# PCIe_USB30_Conn_Panel_Bottom.net
KiCad netlist of a schematic drawn in Altium Designer
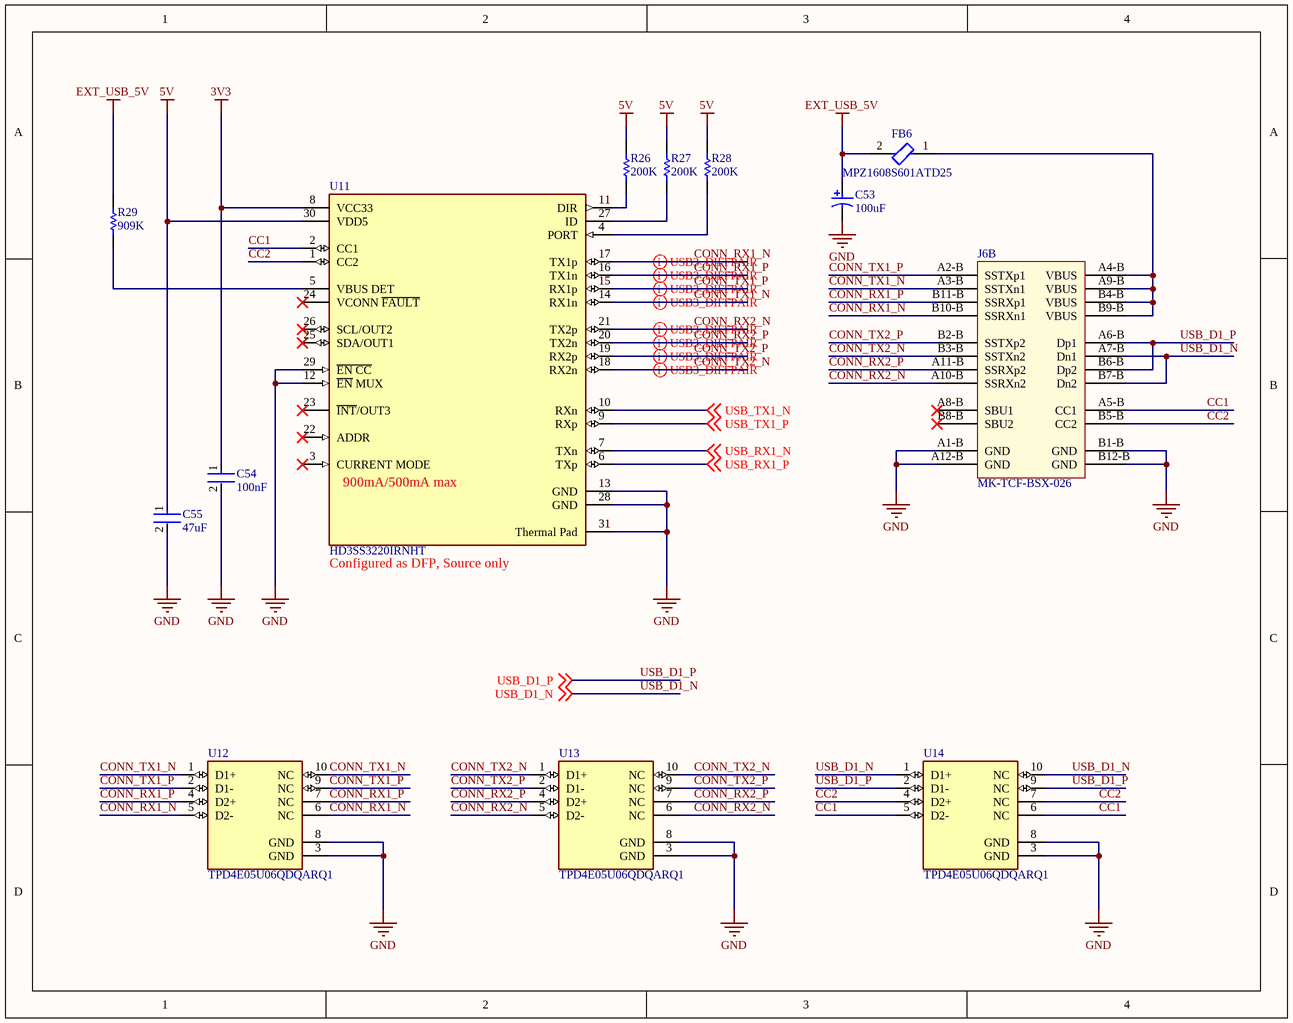
[diagram p0: PCIe_USB30_Conn_Panel_Bottom.SchDoc]

(export (version "E")
  (design (tool "Eeschema 10.0.6"))
  (components
    (comp (ref "C53")
      (value "100uF")
      (footprint "PNSC-EEEFK1C101P_L")
      (fields (field (name "MANUFACTURER") "Panasonic"))
      (libsource (lib "Altium Content Vault") (part "CAP-P-2"))
    )
    (comp (ref "C54")
      (value "100nF")
      (footprint "FP-C0402-BB-MFG")
      (description "CAP CER 0.1UF 10V X5R 0402")
      (fields (field (name "MANUFACTURER") "Kemet") (field (name "TOLERANCE") "0.1"))
      (libsource (lib "Altium Content Vault") (part "b4654b650e69147ec39a6b967a45e02"))
    )
    (comp (ref "C55")
      (value "47uF")
      (footprint "FP-C2012-125-0_2-IPC_B")
      (description "Multilayer Ceramic Capacitors 47μF ±20% 10V X5R SMD 0805")
      (fields (field (name "VOLTAGE") "10V") (field (name "TOLERANCE") "20%"))
      (libsource (lib "Altium Content Vault") (part "b4654b650e69147ec39a6b967a45e02"))
    )
    (comp (ref "FB6")
      (value "MPZ1608S601ATD25")
      (footprint "FP-MPZ1608-0_8-IPC_B")
      (description "Power line Ferrite Bead 600Ω @ 100MHz 1A DCR 0.15Ω AEC-Q200 SMD 0603")
      (fields (field (name "TOLERANCE") "25%"))
      (libsource (lib "Altium Content Vault") (part "5f30dd21d616792df468990f7003faa"))
    )
    (comp (ref "J6")
      (value "MK-TCF-BSX-026")
      (footprint "MK-TCF-BSX-026")
      (libsource (lib "MK-TCF-BSX-026") (part "MK-TCF-BSX-026"))
    )
    (comp (ref "R26")
      (value "200K")
      (footprint "RESC1005X40X25NL05T05")
      (description "Chip Resistor, 200 KOhm, +/- 1%, 100 mW, -55 to 155 degC, 0402 (1005 Metric), RoHS, Tape and Reel")
      (fields (field (name "PARTNUMBER") "ERJ-2RKF2003X") (field (name "TOLERANCE") "1%"))
      (libsource (lib "Altium Content Vault") (part "RES-2"))
    )
    (comp (ref "R27")
      (value "200K")
      (footprint "RESC1005X40X25NL05T05")
      (description "Chip Resistor, 200 KOhm, +/- 1%, 100 mW, -55 to 155 degC, 0402 (1005 Metric), RoHS, Tape and Reel")
      (fields (field (name "PARTNUMBER") "ERJ-2RKF2003X") (field (name "TOLERANCE") "1%"))
      (libsource (lib "Altium Content Vault") (part "RES-2"))
    )
    (comp (ref "R28")
      (value "200K")
      (footprint "RESC1005X40X25NL05T05")
      (description "Chip Resistor, 200 KOhm, +/- 1%, 100 mW, -55 to 155 degC, 0402 (1005 Metric), RoHS, Tape and Reel")
      (fields (field (name "PARTNUMBER") "ERJ-2RKF2003X") (field (name "TOLERANCE") "1%"))
      (libsource (lib "Altium Content Vault") (part "RES-2"))
    )
    (comp (ref "R29")
      (value "909K")
      (footprint "RESC1005X40X25NL05T10")
      (fields (field (name "MANUFACTURER") "Yageo / Phycomp") (field (name "PART NUMBER") "RC0402FR-07909KL"))
      (libsource (lib "Altium Content Vault") (part "RES"))
    )
    (comp (ref "U11")
      (value "HD3SS3220IRNHT")
      (footprint "FP-RNH0030A-MFG")
      (description "USB TYPE-C DRP PORT CONTROLLER W")
      (libsource (lib "Altium Content Vault") (part "bc1798bad1e85e1bff1291d9d73152b"))
    )
    (comp (ref "U12")
      (value "TPD4E05U06QDQARQ1")
      (footprint "FP-DQA0010A-MFG")
      (description "TVS DIODE 5.5V 14V 10USON")
      (fields
        (field (name "OCTOPART") "https://octopart.com/tpd4e05u06qdqarq1-texas+instruments-48523459")
        (field (name "MANUFACTURER") "Texas Instruments")
      )
      (libsource (lib "Altium Content Vault") (part "f11f7ff102fa2b028e1355c732c836d"))
    )
    (comp (ref "U13")
      (value "TPD4E05U06QDQARQ1")
      (footprint "FP-DQA0010A-MFG")
      (description "TVS DIODE 5.5V 14V 10USON")
      (fields
        (field (name "OCTOPART") "https://octopart.com/tpd4e05u06qdqarq1-texas+instruments-48523459")
        (field (name "MANUFACTURER") "Texas Instruments")
      )
      (libsource (lib "Altium Content Vault") (part "f11f7ff102fa2b028e1355c732c836d"))
    )
    (comp (ref "U14")
      (value "TPD4E05U06QDQARQ1")
      (footprint "FP-DQA0010A-MFG")
      (description "TVS DIODE 5.5V 14V 10USON")
      (fields
        (field (name "OCTOPART") "https://octopart.com/tpd4e05u06qdqarq1-texas+instruments-48523459")
        (field (name "MANUFACTURER") "Texas Instruments")
      )
      (libsource (lib "Altium Content Vault") (part "f11f7ff102fa2b028e1355c732c836d"))
    )
  )
  (nets
    (net (code "1") (name "/CC1") (class "Default")
      (node (ref "J6") (pin "A5-B") (pinfunction "CC1_A5-B") (pintype "passive"))
      (node (ref "U11") (pin "2") (pinfunction "CC1_2") (pintype "bidirectional"))
      (node (ref "U14") (pin "5") (pinfunction "D2-_5") (pintype "bidirectional"))
      (node (ref "U14") (pin "6") (pinfunction "NC_6") (pintype "passive"))
    )
    (net (code "2") (name "/CC2") (class "Default")
      (node (ref "J6") (pin "B5-B") (pinfunction "CC2_B5-B") (pintype "passive"))
      (node (ref "U11") (pin "1") (pinfunction "CC2_1") (pintype "bidirectional"))
      (node (ref "U14") (pin "4") (pinfunction "D2+_4") (pintype "bidirectional"))
      (node (ref "U14") (pin "7") (pinfunction "NC_7") (pintype "passive"))
    )
    (net (code "3") (name "/CONN_RX1_N") (class "Default")
      (node (ref "J6") (pin "B10-B") (pinfunction "SSRXn1_B10-B") (pintype "passive"))
      (node (ref "U11") (pin "17") (pinfunction "TX1p_17") (pintype "bidirectional"))
      (node (ref "U12") (pin "5") (pinfunction "D2-_5") (pintype "bidirectional"))
      (node (ref "U12") (pin "6") (pinfunction "NC_6") (pintype "passive"))
    )
    (net (code "4") (name "/CONN_RX1_P") (class "Default")
      (node (ref "J6") (pin "B11-B") (pinfunction "SSRXp1_B11-B") (pintype "passive"))
      (node (ref "U11") (pin "16") (pinfunction "TX1n_16") (pintype "bidirectional"))
      (node (ref "U12") (pin "4") (pinfunction "D2+_4") (pintype "bidirectional"))
      (node (ref "U12") (pin "7") (pinfunction "NC_7") (pintype "passive"))
    )
    (net (code "5") (name "/CONN_RX2_N") (class "Default")
      (node (ref "J6") (pin "A10-B") (pinfunction "SSRXn2_A10-B") (pintype "passive"))
      (node (ref "U11") (pin "21") (pinfunction "TX2p_21") (pintype "bidirectional"))
      (node (ref "U13") (pin "5") (pinfunction "D2-_5") (pintype "bidirectional"))
      (node (ref "U13") (pin "6") (pinfunction "NC_6") (pintype "passive"))
    )
    (net (code "6") (name "/CONN_RX2_P") (class "Default")
      (node (ref "J6") (pin "A11-B") (pinfunction "SSRXp2_A11-B") (pintype "passive"))
      (node (ref "U11") (pin "20") (pinfunction "TX2n_20") (pintype "bidirectional"))
      (node (ref "U13") (pin "4") (pinfunction "D2+_4") (pintype "bidirectional"))
      (node (ref "U13") (pin "7") (pinfunction "NC_7") (pintype "passive"))
    )
    (net (code "7") (name "/CONN_TX1_N") (class "Default")
      (node (ref "J6") (pin "A3-B") (pinfunction "SSTXn1_A3-B") (pintype "passive"))
      (node (ref "U11") (pin "14") (pinfunction "RX1n_14") (pintype "bidirectional"))
      (node (ref "U12") (pin "1") (pinfunction "D1+_1") (pintype "bidirectional"))
      (node (ref "U12") (pin "10") (pinfunction "NC_10") (pintype "bidirectional"))
    )
    (net (code "8") (name "/CONN_TX1_P") (class "Default")
      (node (ref "J6") (pin "A2-B") (pinfunction "SSTXp1_A2-B") (pintype "passive"))
      (node (ref "U11") (pin "15") (pinfunction "RX1p_15") (pintype "bidirectional"))
      (node (ref "U12") (pin "2") (pinfunction "D1-_2") (pintype "bidirectional"))
      (node (ref "U12") (pin "9") (pinfunction "NC_9") (pintype "bidirectional"))
    )
    (net (code "9") (name "/CONN_TX2_N") (class "Default")
      (node (ref "J6") (pin "B3-B") (pinfunction "SSTXn2_B3-B") (pintype "passive"))
      (node (ref "U11") (pin "18") (pinfunction "RX2n_18") (pintype "bidirectional"))
      (node (ref "U13") (pin "1") (pinfunction "D1+_1") (pintype "bidirectional"))
      (node (ref "U13") (pin "10") (pinfunction "NC_10") (pintype "bidirectional"))
    )
    (net (code "10") (name "/CONN_TX2_P") (class "Default")
      (node (ref "J6") (pin "B2-B") (pinfunction "SSTXp2_B2-B") (pintype "passive"))
      (node (ref "U11") (pin "19") (pinfunction "RX2p_19") (pintype "bidirectional"))
      (node (ref "U13") (pin "2") (pinfunction "D1-_2") (pintype "bidirectional"))
      (node (ref "U13") (pin "9") (pinfunction "NC_9") (pintype "bidirectional"))
    )
    (net (code "11") (name "3V3") (class "Default")
      (node (ref "C54") (pin "1") (pinfunction "1_1") (pintype "passive"))
      (node (ref "U11") (pin "8") (pinfunction "VCC33_8") (pintype "power_in"))
    )
    (net (code "12") (name "5V") (class "Default")
      (node (ref "C55") (pin "1") (pinfunction "1_1") (pintype "passive"))
      (node (ref "R26") (pin "2") (pinfunction "2_2") (pintype "passive"))
      (node (ref "R27") (pin "2") (pinfunction "2_2") (pintype "passive"))
      (node (ref "R28") (pin "2") (pinfunction "2_2") (pintype "passive"))
      (node (ref "U11") (pin "30") (pinfunction "VDD5_30") (pintype "power_in"))
    )
    (net (code "13") (name "EXT_USB_5V") (class "Default")
      (node (ref "C53") (pin "1") (pinfunction "1_1") (pintype "passive"))
      (node (ref "FB6") (pin "2") (pinfunction "2_2") (pintype "passive"))
      (node (ref "R29") (pin "2") (pinfunction "2_2") (pintype "passive"))
    )
    (net (code "14") (name "GND") (class "Default")
      (node (ref "C53") (pin "2") (pinfunction "2_2") (pintype "passive"))
      (node (ref "C54") (pin "2") (pinfunction "2_2") (pintype "passive"))
      (node (ref "C55") (pin "2") (pinfunction "2_2") (pintype "passive"))
      (node (ref "J6") (pin "A1-B") (pinfunction "GND_A1-B") (pintype "passive"))
      (node (ref "J6") (pin "A12-B") (pinfunction "GND_A12-B") (pintype "passive"))
      (node (ref "J6") (pin "B1-B") (pinfunction "GND_B1-B") (pintype "passive"))
      (node (ref "J6") (pin "B12-B") (pinfunction "GND_B12-B") (pintype "passive"))
      (node (ref "U11") (pin "12") (pinfunction "~{EN}_MUX_12") (pintype "input"))
      (node (ref "U11") (pin "13") (pinfunction "GND_13") (pintype "power_in"))
      (node (ref "U11") (pin "28") (pinfunction "GND_28") (pintype "power_in"))
      (node (ref "U11") (pin "29") (pinfunction "~{EN_CC}_29") (pintype "input"))
      (node (ref "U11") (pin "31") (pinfunction "Thermal_Pad_31") (pintype "power_in"))
      (node (ref "U12") (pin "3") (pinfunction "GND_3") (pintype "power_in"))
      (node (ref "U12") (pin "8") (pinfunction "GND_8") (pintype "power_in"))
      (node (ref "U13") (pin "3") (pinfunction "GND_3") (pintype "power_in"))
      (node (ref "U13") (pin "8") (pinfunction "GND_8") (pintype "power_in"))
      (node (ref "U14") (pin "3") (pinfunction "GND_3") (pintype "power_in"))
      (node (ref "U14") (pin "8") (pinfunction "GND_8") (pintype "power_in"))
    )
    (net (code "15") (name "Net-(FB6-Pad1)") (class "Default")
      (node (ref "FB6") (pin "1") (pinfunction "1_1") (pintype "passive"))
      (node (ref "J6") (pin "A4-B") (pinfunction "VBUS_A4-B") (pintype "passive"))
      (node (ref "J6") (pin "A9-B") (pinfunction "VBUS_A9-B") (pintype "passive"))
      (node (ref "J6") (pin "B4-B") (pinfunction "VBUS_B4-B") (pintype "passive"))
      (node (ref "J6") (pin "B9-B") (pinfunction "VBUS_B9-B") (pintype "passive"))
    )
    (net (code "16") (name "Net-(U11-DIR)") (class "Default")
      (node (ref "R26") (pin "1") (pinfunction "1_1") (pintype "passive"))
      (node (ref "U11") (pin "11") (pinfunction "DIR_11") (pintype "output"))
    )
    (net (code "17") (name "Net-(U11-ID)") (class "Default")
      (node (ref "R27") (pin "1") (pinfunction "1_1") (pintype "passive"))
      (node (ref "U11") (pin "27") (pinfunction "ID_27") (pintype "open_collector"))
    )
    (net (code "18") (name "Net-(U11-PORT)") (class "Default")
      (node (ref "R28") (pin "1") (pinfunction "1_1") (pintype "passive"))
      (node (ref "U11") (pin "4") (pinfunction "PORT_4") (pintype "input"))
    )
    (net (code "19") (name "Net-(U11-VBUS_DET)") (class "Default")
      (node (ref "R29") (pin "1") (pinfunction "1_1") (pintype "passive"))
      (node (ref "U11") (pin "5") (pinfunction "VBUS_DET_5") (pintype "power_in"))
    )
    (net (code "20") (name "USB_D1_N") (class "Default")
      (node (ref "J6") (pin "A7-B") (pinfunction "Dn1_A7-B") (pintype "passive"))
      (node (ref "J6") (pin "B7-B") (pinfunction "Dn2_B7-B") (pintype "passive"))
      (node (ref "U14") (pin "1") (pinfunction "D1+_1") (pintype "bidirectional"))
      (node (ref "U14") (pin "10") (pinfunction "NC_10") (pintype "bidirectional"))
    )
    (net (code "21") (name "USB_D1_P") (class "Default")
      (node (ref "J6") (pin "A6-B") (pinfunction "Dp1_A6-B") (pintype "passive"))
      (node (ref "J6") (pin "B6-B") (pinfunction "Dp2_B6-B") (pintype "passive"))
      (node (ref "U14") (pin "2") (pinfunction "D1-_2") (pintype "bidirectional"))
      (node (ref "U14") (pin "9") (pinfunction "NC_9") (pintype "bidirectional"))
    )
    (net (code "22") (name "USB_RX1_N") (class "Default")
      (node (ref "U11") (pin "7") (pinfunction "TXn_7") (pintype "bidirectional"))
    )
    (net (code "23") (name "USB_RX1_P") (class "Default")
      (node (ref "U11") (pin "6") (pinfunction "TXp_6") (pintype "bidirectional"))
    )
    (net (code "24") (name "USB_TX1_N") (class "Default")
      (node (ref "U11") (pin "10") (pinfunction "RXn_10") (pintype "bidirectional"))
    )
    (net (code "25") (name "USB_TX1_P") (class "Default")
      (node (ref "U11") (pin "9") (pinfunction "RXp_9") (pintype "bidirectional"))
    )
    (net (code "26") (name "unconnected-(J6B-SBU1-PadA8-B)") (class "Default")
      (node (ref "J6") (pin "A8-B") (pinfunction "SBU1_A8-B") (pintype "passive+no_connect"))
    )
    (net (code "27") (name "unconnected-(J6B-SBU2-PadB8-B)") (class "Default")
      (node (ref "J6") (pin "B8-B") (pinfunction "SBU2_B8-B") (pintype "passive+no_connect"))
    )
    (net (code "28") (name "unconnected-(U11-ADDR-Pad22)") (class "Default")
      (node (ref "U11") (pin "22") (pinfunction "ADDR_22") (pintype "input+no_connect"))
    )
    (net (code "29") (name "unconnected-(U11-CURRENT_MODE-Pad3)") (class "Default")
      (node (ref "U11") (pin "3") (pinfunction "CURRENT_MODE_3") (pintype "input+no_connect"))
    )
    (net (code "30") (name "unconnected-(U11-SCL{slash}OUT2-Pad26)") (class "Default")
      (node (ref "U11") (pin "26") (pinfunction "SCL/OUT2_26") (pintype "bidirectional+no_connect"))
    )
    (net (code "31") (name "unconnected-(U11-SDA{slash}OUT1-Pad25)") (class "Default")
      (node (ref "U11") (pin "25") (pinfunction "SDA/OUT1_25") (pintype "bidirectional+no_connect"))
    )
    (net (code "32") (name "unconnected-(U11-VCONN_~{FAULT}-Pad24)") (class "Default")
      (node (ref "U11") (pin "24") (pinfunction "VCONN_~{FAULT}_24") (pintype "open_collector+no_connect"))
    )
    (net (code "33") (name "unconnected-(U11-~{INT}{slash}OUT3-Pad23)") (class "Default")
      (node (ref "U11") (pin "23") (pinfunction "~{INT}/OUT3_23") (pintype "open_collector+no_connect"))
    )
  )
)
